# BaseFunctions.net
KiCad netlist of a schematic drawn in Altium Designer
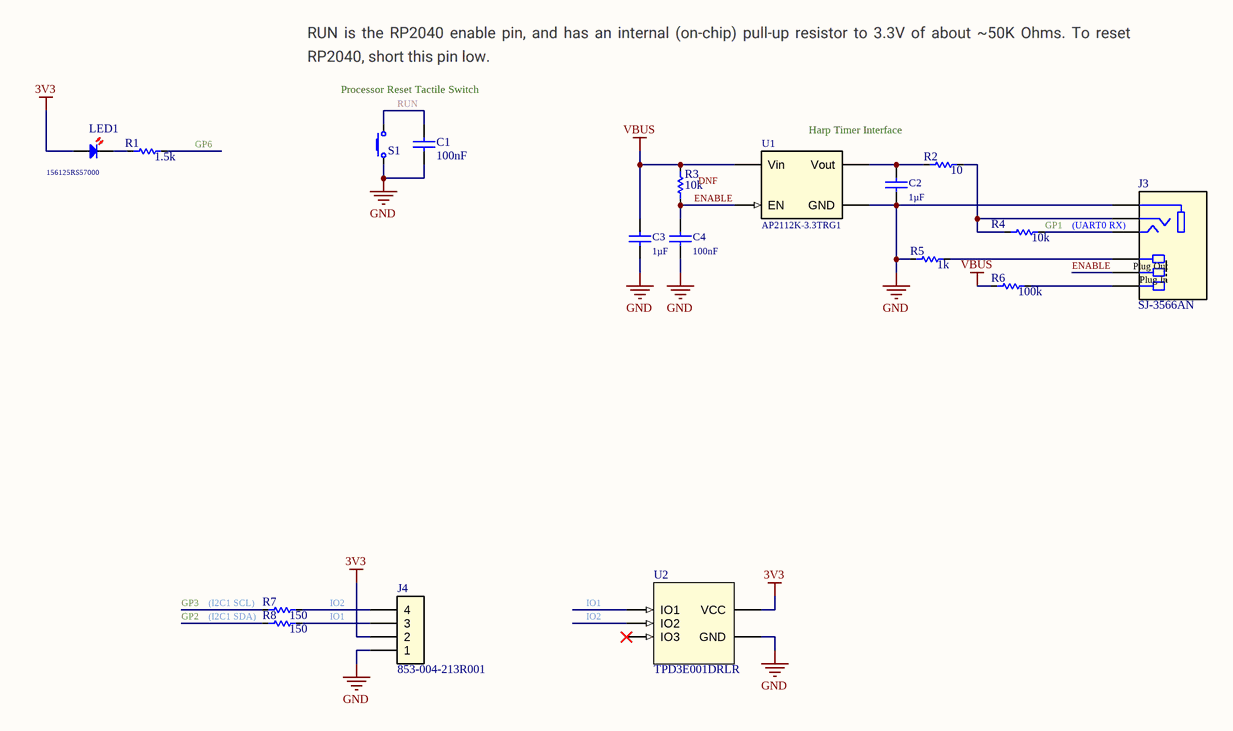
[diagram p0: BaseFunctions.SchDoc]

(export (version "E")
  (design (tool "Eeschema 10.0.6"))
  (components
    (comp (ref "C1")
      (value "100nF")
      (footprint "FP-GRM188-0_1-e0_2_0_5-IPC_B")
      (description "0.1µF ±10% 100V Ceramic Capacitor X7R 0603 (1608 Metric)")
      (fields (field (name "TOLERANCE") "10%") (field (name "VOLTAGE") "100V"))
      (libsource (lib "Sainsbury Wellcome Centre") (part "Cap"))
    )
    (comp (ref "C2")
      (value "1µF")
      (footprint "FP-GRM188-0_1-e0_2_0_5-IPC_B")
      (description "1µF ±10% 25V Ceramic Capacitor X7R 0603 (1608 Metric)")
      (fields (field (name "VOLTAGE") "25V") (field (name "TOLERANCE") "10%"))
      (libsource (lib "Sainsbury Wellcome Centre") (part "Cap"))
    )
    (comp (ref "C3")
      (value "1µF")
      (footprint "FP-GRM188-0_1-e0_2_0_5-IPC_B")
      (description "1µF ±10% 25V Ceramic Capacitor X7R 0603 (1608 Metric)")
      (fields (field (name "VOLTAGE") "25V") (field (name "TOLERANCE") "10%"))
      (libsource (lib "Sainsbury Wellcome Centre") (part "Cap"))
    )
    (comp (ref "C4")
      (value "100nF")
      (footprint "FP-GRM188-0_1-e0_2_0_5-IPC_B")
      (description "0.1µF ±10% 100V Ceramic Capacitor X7R 0603 (1608 Metric)")
      (fields (field (name "TOLERANCE") "10%") (field (name "VOLTAGE") "100V"))
      (libsource (lib "Sainsbury Wellcome Centre") (part "Cap"))
    )
    (comp (ref "J3")
      (value "SJ-3566AN")
      (footprint "CUI_SJ-3566AN - RM")
      (description "3.5 mm, Stereo, Right Angle, Through Hole, SPDT Switch, Audio Jack Connector")
      (fields (field (name "PARTNUMBER") "SJ-3566AN"))
      (libsource (lib "Sainsbury Wellcome Centre") (part "SJ-3566AN-Symbol-1"))
    )
    (comp (ref "J4")
      (value "853-004-213R001")
      (footprint "853-004-213R00Y")
      (description "CONN PLUG FMALE 4POS GOLD SOLDER")
      (libsource (lib "Sainsbury Wellcome Centre") (part "Jack 4x1"))
    )
    (comp (ref "LED1")
      (value "156125RS57000")
      (footprint "WL-SMRD_1205_normal use")
      (description "Single Color LED")
      (fields (field (name "PARTNUMBER") "156125RS57000"))
      (libsource (lib "Sainsbury Wellcome Centre") (part "LED-RED"))
    )
    (comp (ref "R1")
      (value "1.5k")
      (footprint "FP-CPF0603-IPC_B")
      (description "Surface Mount Resistor 1k5 Ohm 1/16 W 0.1% 0603 (1608 Metric)")
      (fields (field (name "TOLERANCE") "0.1%") (field (name "Comment") "R0603-1k5-1/16W-0.1%"))
      (libsource (lib "Sainsbury Wellcome Centre") (part "Res"))
    )
    (comp (ref "R2")
      (value "10")
      (footprint "FP-CPF0603-IPC_B")
      (description "Surface Mount Resistor 10 Ohm 1/16 W 0.1% 0603 (1608 Metric)")
      (fields (field (name "TOLERANCE") "0.1%") (field (name "Comment") "R0603-10R-1/16W-0.1%"))
      (libsource (lib "Sainsbury Wellcome Centre") (part "Res"))
    )
    (comp (ref "R3")
      (value "10k")
      (footprint "FP-CPF0603-IPC_B")
      (description "Surface Mount Resistor 10k Ohm 1/16 W 0.1% 0603 (1608 Metric)")
      (fields (field (name "TOLERANCE") "0.1%") (field (name "Comment") "R0603-10k-1/16W-0.1%"))
      (libsource (lib "Sainsbury Wellcome Centre") (part "Res"))
    )
    (comp (ref "R4")
      (value "10k")
      (footprint "FP-CPF0603-IPC_B")
      (description "Surface Mount Resistor 10k Ohm 1/16 W 0.1% 0603 (1608 Metric)")
      (fields (field (name "TOLERANCE") "0.1%") (field (name "Comment") "R0603-10k-1/16W-0.1%"))
      (libsource (lib "Sainsbury Wellcome Centre") (part "Res"))
    )
    (comp (ref "R5")
      (value "1k")
      (footprint "FP-CPF0603-IPC_B")
      (description "Surface Mount Resistor 1k Ohm 1/16 W 0.1% 0603 (1608 Metric)")
      (fields (field (name "TOLERANCE") "0.1%") (field (name "Comment") "R0603-1k-1/16W-0.1%"))
      (libsource (lib "Sainsbury Wellcome Centre") (part "Res"))
    )
    (comp (ref "R6")
      (value "100k")
      (footprint "FP-CPF0603-IPC_B")
      (description "Surface Mount Resistor 100k Ohm 1/16 W 0.1% 0603 (1608 Metric)")
      (fields (field (name "TOLERANCE") "0.1%") (field (name "Comment") "R0603-100k-1/16W-0.1%"))
      (libsource (lib "Sainsbury Wellcome Centre") (part "Res"))
    )
    (comp (ref "R7")
      (value "150")
      (footprint "FP-CPF0603-IPC_B")
      (description "Surface Mount Resistor 150 Ohm 1/16 W 0.1% 0603 (1608 Metric)")
      (fields (field (name "TOLERANCE") "0.1%") (field (name "Comment") "R0603-150R-1/16W-0.1%"))
      (libsource (lib "Sainsbury Wellcome Centre") (part "Res"))
    )
    (comp (ref "R8")
      (value "150")
      (footprint "FP-CPF0603-IPC_B")
      (description "Surface Mount Resistor 150 Ohm 1/16 W 0.1% 0603 (1608 Metric)")
      (fields (field (name "TOLERANCE") "0.1%") (field (name "Comment") "R0603-150R-1/16W-0.1%"))
      (libsource (lib "Sainsbury Wellcome Centre") (part "Res"))
    )
    (comp (ref "S1")
      (value "PTS645VM83-2LFS")
      (footprint "PTS645VM83-2LFS")
      (libsource (lib "Sainsbury Wellcome Centre") (part "Tactile Switch SPST N.O."))
    )
    (comp (ref "U1")
      (value "AP2112K-3.3TRG1")
      (footprint "FP-SOT25-IPC_B")
      (description "Fixed Positive LDO Regulator, 3.3V, 0.4V Dropout, CMOS, PDSO5")
      (fields (field (name "PARTNUMBER") "AP2112K-3.3TRG1"))
      (libsource (lib "Sainsbury Wellcome Centre") (part "AP2112-SOT25"))
    )
    (comp (ref "U2")
      (value "TPD3E001DRLR")
      (footprint "DRL5_TEX")
      (description "Low-Capacitance 3-Channel +/-15KV ESD-Protection Array for High-Speed Data Interfaces 5-SOT-5X3")
      (fields (field (name "PARTNUMBER") "TPD3E001DRLR"))
      (libsource (lib "Sainsbury Wellcome Centre") (part "TPD3E001DRLR"))
    )
  )
  (nets
    (net (code "1") (name "/ENABLE") (class "Default")
      (node (ref "C4") (pin "2") (pinfunction "2_2") (pintype "passive"))
      (node (ref "J3") (pin "5") (pinfunction "5_5") (pintype "passive"))
      (node (ref "R3") (pin "1") (pinfunction "1_1") (pintype "passive"))
      (node (ref "U1") (pin "3") (pinfunction "EN_3") (pintype "input"))
    )
    (net (code "2") (name "/GP1") (class "Default")
      (node (ref "J3") (pin "2") (pinfunction "2_2") (pintype "passive"))
      (node (ref "R4") (pin "2") (pinfunction "2_2") (pintype "passive"))
    )
    (net (code "3") (name "/GP2") (class "Default")
      (node (ref "R8") (pin "1") (pinfunction "1_1") (pintype "passive"))
    )
    (net (code "4") (name "/GP3") (class "Default")
      (node (ref "R7") (pin "1") (pinfunction "1_1") (pintype "passive"))
    )
    (net (code "5") (name "/GP6") (class "Default")
      (node (ref "R1") (pin "2") (pinfunction "2_2") (pintype "passive"))
    )
    (net (code "6") (name "/IO1") (class "Default")
      (node (ref "J4") (pin "3") (pinfunction "3_3") (pintype "passive"))
      (node (ref "R8") (pin "2") (pinfunction "2_2") (pintype "passive"))
      (node (ref "U2") (pin "1") (pinfunction "IO1_1") (pintype "input"))
    )
    (net (code "7") (name "/IO2") (class "Default")
      (node (ref "J4") (pin "4") (pinfunction "4_4") (pintype "passive"))
      (node (ref "R7") (pin "2") (pinfunction "2_2") (pintype "passive"))
      (node (ref "U2") (pin "2") (pinfunction "IO2_2") (pintype "input"))
    )
    (net (code "8") (name "/RUN") (class "Default")
      (node (ref "C1") (pin "2") (pinfunction "2_2") (pintype "passive"))
      (node (ref "S1") (pin "2") (pinfunction "2_2") (pintype "passive"))
    )
    (net (code "9") (name "3V3") (class "Default")
      (node (ref "J4") (pin "2") (pinfunction "2_2") (pintype "passive"))
      (node (ref "LED1") (pin "1") (pinfunction "A_1") (pintype "passive"))
      (node (ref "U2") (pin "5") (pinfunction "VCC_5") (pintype "power_in"))
    )
    (net (code "10") (name "GND") (class "Default")
      (node (ref "C1") (pin "1") (pinfunction "1_1") (pintype "passive"))
      (node (ref "C2") (pin "1") (pinfunction "1_1") (pintype "passive"))
      (node (ref "C3") (pin "1") (pinfunction "1_1") (pintype "passive"))
      (node (ref "C4") (pin "1") (pinfunction "1_1") (pintype "passive"))
      (node (ref "J3") (pin "1") (pinfunction "1_1") (pintype "passive"))
      (node (ref "J4") (pin "1") (pinfunction "1_1") (pintype "passive"))
      (node (ref "R5") (pin "1") (pinfunction "1_1") (pintype "passive"))
      (node (ref "S1") (pin "1") (pinfunction "1_1") (pintype "passive"))
      (node (ref "U1") (pin "2") (pinfunction "GND_2") (pintype "power_in"))
      (node (ref "U2") (pin "3") (pinfunction "GND_3") (pintype "power_in"))
    )
    (net (code "11") (name "Net-(J3-Pad3)") (class "Default")
      (node (ref "J3") (pin "3") (pinfunction "3_3") (pintype "passive"))
      (node (ref "R2") (pin "2") (pinfunction "2_2") (pintype "passive"))
      (node (ref "R4") (pin "1") (pinfunction "1_1") (pintype "passive"))
    )
    (net (code "12") (name "Net-(J3-Pad4)") (class "Default")
      (node (ref "J3") (pin "4") (pinfunction "4_4") (pintype "passive"))
      (node (ref "R5") (pin "2") (pinfunction "2_2") (pintype "passive"))
    )
    (net (code "13") (name "Net-(J3-Pad6)") (class "Default")
      (node (ref "J3") (pin "6") (pinfunction "6_6") (pintype "passive"))
      (node (ref "R6") (pin "2") (pinfunction "2_2") (pintype "passive"))
    )
    (net (code "14") (name "Net-(LED1-K)") (class "Default")
      (node (ref "LED1") (pin "2") (pinfunction "K_2") (pintype "passive"))
      (node (ref "R1") (pin "1") (pinfunction "1_1") (pintype "passive"))
    )
    (net (code "15") (name "Net-(U1-Vout)") (class "Default")
      (node (ref "C2") (pin "2") (pinfunction "2_2") (pintype "passive"))
      (node (ref "R2") (pin "1") (pinfunction "1_1") (pintype "passive"))
      (node (ref "U1") (pin "5") (pinfunction "Vout_5") (pintype "power_in"))
    )
    (net (code "16") (name "VBUS") (class "Default")
      (node (ref "C3") (pin "2") (pinfunction "2_2") (pintype "passive"))
      (node (ref "R3") (pin "2") (pinfunction "2_2") (pintype "passive"))
      (node (ref "R6") (pin "1") (pinfunction "1_1") (pintype "passive"))
      (node (ref "U1") (pin "1") (pinfunction "Vin_1") (pintype "power_in"))
    )
    (net (code "17") (name "unconnected-(U2-IO3-Pad4)") (class "Default")
      (node (ref "U2") (pin "4") (pinfunction "IO3_4") (pintype "input+no_connect"))
    )
  )
)
